# 08_EPROM_UNIQUE_SERIAL.net
KiCad netlist of a schematic drawn in Altium Designer
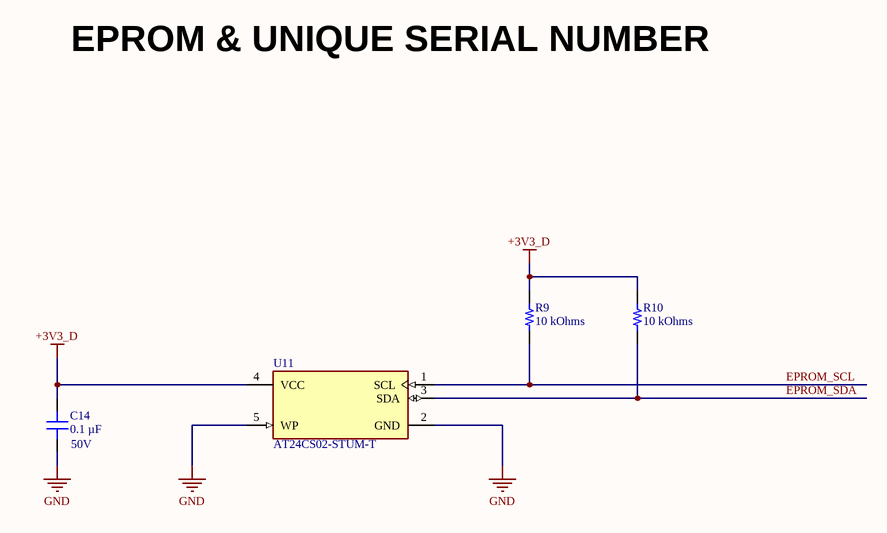
[diagram p0: 08_EPROM_UNIQUE_SERIAL.SchDoc]

(export (version "E")
  (design (tool "Eeschema 10.0.6"))
  (components
    (comp (ref "C14")
      (value "0.1 µF")
      (footprint "CAP 0402_1005")
      (description "CAP CER 0.1UF 50V X7R 0402")
      (fields
        (field (name "PART NUMBER") "GCM155R71H104KE02J")
        (field (name "CAPACITANCE") "0.1 µF")
        (field (name "MANUFACTURER") "Murata Electronics")
        (field (name "VOLTAGE - RATED") "50V")
      )
      (libsource (lib "Celestial Altium Library - altium_library") (part "Capacitor"))
    )
    (comp (ref "R9")
      (value "10 kOhms")
      (footprint "RES 0402_1005")
      (description "RES 10K OHM 1% 1/16W 0402")
      (fields (field (name "PART NUMBER") "RC0402FR-0710KL") (field (name "MANUFACTURER") "Yageo"))
      (libsource (lib "Celestial Altium Library - altium_library") (part "Resistor"))
    )
    (comp (ref "R10")
      (value "10 kOhms")
      (footprint "RES 0402_1005")
      (description "RES 10K OHM 1% 1/16W 0402")
      (fields (field (name "PART NUMBER") "RC0402FR-0710KL") (field (name "MANUFACTURER") "Yageo"))
      (libsource (lib "Celestial Altium Library - altium_library") (part "Resistor"))
    )
    (comp (ref "U11")
      (value "AT24CS02-STUM-T")
      (footprint "FP-C04-21344-MFG")
      (description "IC EEPROM 2K I2C 1MHZ SOT23-5")
      (libsource (lib "Altium Content Vault") (part "e8975df7c73661f1596824d25bb16d1"))
    )
  )
  (nets
    (net (code "1") (name "+3V3_D") (class "Default")
      (node (ref "C14") (pin "2") (pinfunction "2_2") (pintype "passive"))
      (node (ref "R10") (pin "2") (pinfunction "2_2") (pintype "passive"))
      (node (ref "R9") (pin "2") (pinfunction "2_2") (pintype "passive"))
      (node (ref "U11") (pin "4") (pinfunction "VCC_4") (pintype "power_in"))
    )
    (net (code "2") (name "/EPROM_SCL") (class "Default")
      (node (ref "R9") (pin "1") (pinfunction "1_1") (pintype "passive"))
      (node (ref "U11") (pin "1") (pinfunction "SCL_1") (pintype "input"))
    )
    (net (code "3") (name "/EPROM_SDA") (class "Default")
      (node (ref "R10") (pin "1") (pinfunction "1_1") (pintype "passive"))
      (node (ref "U11") (pin "3") (pinfunction "SDA_3") (pintype "bidirectional"))
    )
    (net (code "4") (name "GND") (class "Default")
      (node (ref "C14") (pin "1") (pinfunction "1_1") (pintype "passive"))
      (node (ref "U11") (pin "2") (pinfunction "GND_2") (pintype "power_in"))
      (node (ref "U11") (pin "5") (pinfunction "WP_5") (pintype "input"))
    )
  )
)
